# Vehicle_Circuit.net
KiCad netlist of a schematic drawn in Altium Designer
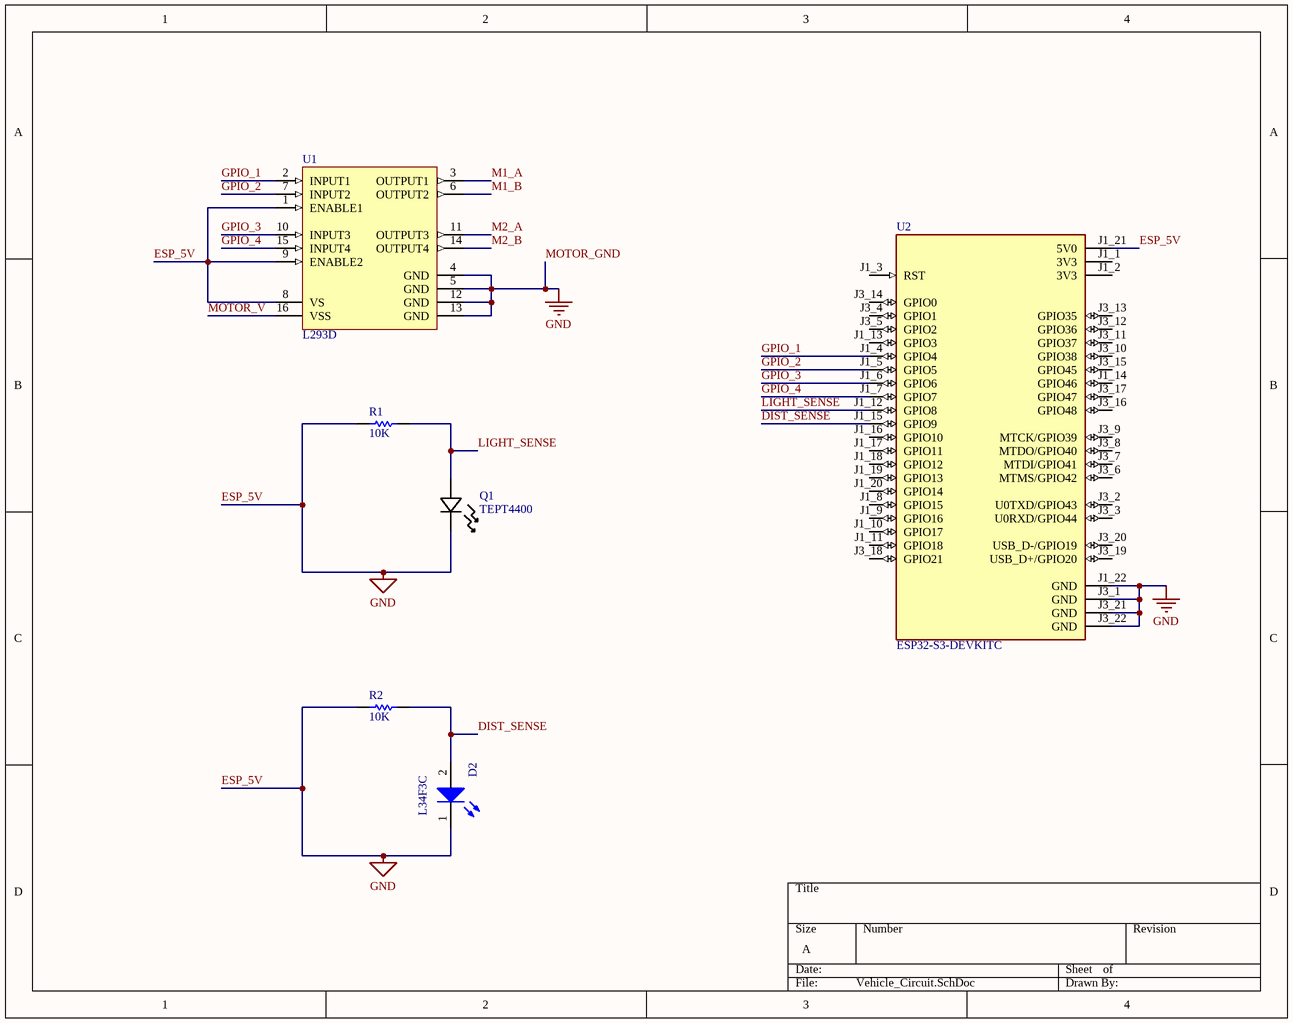
[diagram p0: Vehicle_Circuit.SchDoc]

(export (version "E")
  (design (tool "Eeschema 10.0.6"))
  (components
    (comp (ref "D2")
      (value "L34F3C")
      (footprint "WL-TIRW_D3.9H5.3")
      (description "WL-TIRW THT Infrared Round Waterclear")
      (libsource (lib "Altium Content Vault") (part "LED_Infrared_2A-1K"))
    )
    (comp (ref "Q1")
      (value "TEPT4400")
      (footprint "LED_TEPT4400_VIS")
      (description "PHOTO TRANS. 3MM  30DEG-e4")
      (fields (field (name "COPYRIGHT") "Copyright (C) 2026 Ultra Librarian. All rights reserved."))
      (libsource (lib "TEPT4400") (part "TEPT4400"))
    )
    (comp (ref "R1")
      (value "10K")
      (description "Resistor")
      (libsource (lib "Simulation Generic Components") (part "Resistor"))
    )
    (comp (ref "R2")
      (value "10K")
      (description "Resistor")
      (libsource (lib "Simulation Generic Components") (part "Resistor"))
    )
    (comp (ref "U1")
      (value "L293D")
      (footprint "STM-L293D-16")
      (description "Push-Pull Four Channel Driver with Diode, 4.5 to 36 V, -40 to 150 degC, 16-Pin PDIP, RoHS, Tube")
      (fields (field (name "MANUFACTURER") "STMicroelectronics"))
      (libsource (lib "Altium Content Vault") (part "STM-L293D-16"))
    )
    (comp (ref "U2")
      (value "ESP32-S3-DEVKITC")
      (footprint "XCVR_ESP32-S3-DEVKITC-1-N16R8V")
      (fields (field (name "MF") "Espressif Systems") (field (name "MP") "ESP32-S3-DEVKITC-1-N16R8V"))
      (libsource (lib "ESP32-S3-DEVKITC-1-N16R8V") (part "ESP32-S3-DEVKITC-1-N16R8V"))
    )
  )
  (nets
    (net (code "1") (name "/DIST_SENSE") (class "Default")
      (node (ref "D2") (pin "2") (pinfunction "A_2") (pintype "passive"))
      (node (ref "R2") (pin "2") (pinfunction "2_2") (pintype "passive"))
      (node (ref "U2") (pin "J1_15") (pinfunction "GPIO9_J1_15") (pintype "bidirectional"))
    )
    (net (code "2") (name "/GPIO_1") (class "Default")
      (node (ref "U1") (pin "2") (pinfunction "INPUT1_2") (pintype "input"))
      (node (ref "U2") (pin "J1_4") (pinfunction "GPIO4_J1_4") (pintype "bidirectional"))
    )
    (net (code "3") (name "/GPIO_2") (class "Default")
      (node (ref "U1") (pin "7") (pinfunction "INPUT2_7") (pintype "input"))
      (node (ref "U2") (pin "J1_5") (pinfunction "GPIO5_J1_5") (pintype "bidirectional"))
    )
    (net (code "4") (name "/GPIO_3") (class "Default")
      (node (ref "U1") (pin "10") (pinfunction "INPUT3_10") (pintype "input"))
      (node (ref "U2") (pin "J1_6") (pinfunction "GPIO6_J1_6") (pintype "bidirectional"))
    )
    (net (code "5") (name "/GPIO_4") (class "Default")
      (node (ref "U1") (pin "15") (pinfunction "INPUT4_15") (pintype "input"))
      (node (ref "U2") (pin "J1_7") (pinfunction "GPIO7_J1_7") (pintype "bidirectional"))
    )
    (net (code "6") (name "/LIGHT_SENSE") (class "Default")
      (node (ref "Q1") (pin "2") (pinfunction "2_2") (pintype "passive"))
      (node (ref "R1") (pin "2") (pinfunction "2_2") (pintype "passive"))
      (node (ref "U2") (pin "J1_12") (pinfunction "GPIO8_J1_12") (pintype "bidirectional"))
    )
    (net (code "7") (name "/M1_A") (class "Default")
      (node (ref "U1") (pin "3") (pinfunction "OUTPUT1_3") (pintype "output"))
    )
    (net (code "8") (name "/M1_B") (class "Default")
      (node (ref "U1") (pin "6") (pinfunction "OUTPUT2_6") (pintype "output"))
    )
    (net (code "9") (name "/M2_A") (class "Default")
      (node (ref "U1") (pin "11") (pinfunction "OUTPUT3_11") (pintype "output"))
    )
    (net (code "10") (name "/M2_B") (class "Default")
      (node (ref "U1") (pin "14") (pinfunction "OUTPUT4_14") (pintype "output"))
    )
    (net (code "11") (name "/MOTOR_V") (class "Default")
      (node (ref "U1") (pin "16") (pinfunction "VSS_16") (pintype "power_in"))
    )
    (net (code "12") (name "GND") (class "Default")
      (node (ref "D2") (pin "1") (pinfunction "K_1") (pintype "passive"))
      (node (ref "Q1") (pin "1") (pinfunction "1_1") (pintype "passive"))
      (node (ref "R1") (pin "1") (pinfunction "1_1") (pintype "passive"))
      (node (ref "R2") (pin "1") (pinfunction "1_1") (pintype "passive"))
      (node (ref "U1") (pin "1") (pinfunction "ENABLE1_1") (pintype "input"))
      (node (ref "U1") (pin "12") (pinfunction "GND_12") (pintype "power_in"))
      (node (ref "U1") (pin "13") (pinfunction "GND_13") (pintype "power_in"))
      (node (ref "U1") (pin "4") (pinfunction "GND_4") (pintype "power_in"))
      (node (ref "U1") (pin "5") (pinfunction "GND_5") (pintype "power_in"))
      (node (ref "U1") (pin "8") (pinfunction "VS_8") (pintype "power_in"))
      (node (ref "U1") (pin "9") (pinfunction "ENABLE2_9") (pintype "input"))
      (node (ref "U2") (pin "J1_21") (pinfunction "5V0_J1_21") (pintype "power_in"))
      (node (ref "U2") (pin "J1_22") (pinfunction "GND_J1_22") (pintype "power_in"))
      (node (ref "U2") (pin "J3_1") (pinfunction "GND_J3_1") (pintype "power_in"))
      (node (ref "U2") (pin "J3_21") (pinfunction "GND_J3_21") (pintype "power_in"))
      (node (ref "U2") (pin "J3_22") (pinfunction "GND_J3_22") (pintype "power_in"))
    )
    (net (code "13") (name "unconnected-(U2-3V3-PadJ1_1)") (class "Default")
      (node (ref "U2") (pin "J1_1") (pinfunction "3V3_J1_1") (pintype "power_in"))
    )
    (net (code "14") (name "unconnected-(U2-3V3-PadJ1_2)") (class "Default")
      (node (ref "U2") (pin "J1_2") (pinfunction "3V3_J1_2") (pintype "power_in"))
    )
    (net (code "15") (name "unconnected-(U2-GPIO0-PadJ3_14)") (class "Default")
      (node (ref "U2") (pin "J3_14") (pinfunction "GPIO0_J3_14") (pintype "bidirectional"))
    )
    (net (code "16") (name "unconnected-(U2-GPIO1-PadJ3_4)") (class "Default")
      (node (ref "U2") (pin "J3_4") (pinfunction "GPIO1_J3_4") (pintype "bidirectional"))
    )
    (net (code "17") (name "unconnected-(U2-GPIO2-PadJ3_5)") (class "Default")
      (node (ref "U2") (pin "J3_5") (pinfunction "GPIO2_J3_5") (pintype "bidirectional"))
    )
    (net (code "18") (name "unconnected-(U2-GPIO3-PadJ1_13)") (class "Default")
      (node (ref "U2") (pin "J1_13") (pinfunction "GPIO3_J1_13") (pintype "bidirectional"))
    )
    (net (code "19") (name "unconnected-(U2-GPIO10-PadJ1_16)") (class "Default")
      (node (ref "U2") (pin "J1_16") (pinfunction "GPIO10_J1_16") (pintype "bidirectional"))
    )
    (net (code "20") (name "unconnected-(U2-GPIO11-PadJ1_17)") (class "Default")
      (node (ref "U2") (pin "J1_17") (pinfunction "GPIO11_J1_17") (pintype "bidirectional"))
    )
    (net (code "21") (name "unconnected-(U2-GPIO12-PadJ1_18)") (class "Default")
      (node (ref "U2") (pin "J1_18") (pinfunction "GPIO12_J1_18") (pintype "bidirectional"))
    )
    (net (code "22") (name "unconnected-(U2-GPIO13-PadJ1_19)") (class "Default")
      (node (ref "U2") (pin "J1_19") (pinfunction "GPIO13_J1_19") (pintype "bidirectional"))
    )
    (net (code "23") (name "unconnected-(U2-GPIO14-PadJ1_20)") (class "Default")
      (node (ref "U2") (pin "J1_20") (pinfunction "GPIO14_J1_20") (pintype "bidirectional"))
    )
    (net (code "24") (name "unconnected-(U2-GPIO15-PadJ1_8)") (class "Default")
      (node (ref "U2") (pin "J1_8") (pinfunction "GPIO15_J1_8") (pintype "bidirectional"))
    )
    (net (code "25") (name "unconnected-(U2-GPIO16-PadJ1_9)") (class "Default")
      (node (ref "U2") (pin "J1_9") (pinfunction "GPIO16_J1_9") (pintype "bidirectional"))
    )
    (net (code "26") (name "unconnected-(U2-GPIO17-PadJ1_10)") (class "Default")
      (node (ref "U2") (pin "J1_10") (pinfunction "GPIO17_J1_10") (pintype "bidirectional"))
    )
    (net (code "27") (name "unconnected-(U2-GPIO18-PadJ1_11)") (class "Default")
      (node (ref "U2") (pin "J1_11") (pinfunction "GPIO18_J1_11") (pintype "bidirectional"))
    )
    (net (code "28") (name "unconnected-(U2-GPIO21-PadJ3_18)") (class "Default")
      (node (ref "U2") (pin "J3_18") (pinfunction "GPIO21_J3_18") (pintype "bidirectional"))
    )
    (net (code "29") (name "unconnected-(U2-GPIO35-PadJ3_13)") (class "Default")
      (node (ref "U2") (pin "J3_13") (pinfunction "GPIO35_J3_13") (pintype "bidirectional"))
    )
    (net (code "30") (name "unconnected-(U2-GPIO36-PadJ3_12)") (class "Default")
      (node (ref "U2") (pin "J3_12") (pinfunction "GPIO36_J3_12") (pintype "bidirectional"))
    )
    (net (code "31") (name "unconnected-(U2-GPIO37-PadJ3_11)") (class "Default")
      (node (ref "U2") (pin "J3_11") (pinfunction "GPIO37_J3_11") (pintype "bidirectional"))
    )
    (net (code "32") (name "unconnected-(U2-GPIO38-PadJ3_10)") (class "Default")
      (node (ref "U2") (pin "J3_10") (pinfunction "GPIO38_J3_10") (pintype "bidirectional"))
    )
    (net (code "33") (name "unconnected-(U2-GPIO45-PadJ3_15)") (class "Default")
      (node (ref "U2") (pin "J3_15") (pinfunction "GPIO45_J3_15") (pintype "bidirectional"))
    )
    (net (code "34") (name "unconnected-(U2-GPIO46-PadJ1_14)") (class "Default")
      (node (ref "U2") (pin "J1_14") (pinfunction "GPIO46_J1_14") (pintype "bidirectional"))
    )
    (net (code "35") (name "unconnected-(U2-GPIO47-PadJ3_17)") (class "Default")
      (node (ref "U2") (pin "J3_17") (pinfunction "GPIO47_J3_17") (pintype "bidirectional"))
    )
    (net (code "36") (name "unconnected-(U2-GPIO48-PadJ3_16)") (class "Default")
      (node (ref "U2") (pin "J3_16") (pinfunction "GPIO48_J3_16") (pintype "bidirectional"))
    )
    (net (code "37") (name "unconnected-(U2-MTCK{slash}GPIO39-PadJ3_9)") (class "Default")
      (node (ref "U2") (pin "J3_9") (pinfunction "MTCK/GPIO39_J3_9") (pintype "bidirectional"))
    )
    (net (code "38") (name "unconnected-(U2-MTDI{slash}GPIO41-PadJ3_7)") (class "Default")
      (node (ref "U2") (pin "J3_7") (pinfunction "MTDI/GPIO41_J3_7") (pintype "bidirectional"))
    )
    (net (code "39") (name "unconnected-(U2-MTDO{slash}GPIO40-PadJ3_8)") (class "Default")
      (node (ref "U2") (pin "J3_8") (pinfunction "MTDO/GPIO40_J3_8") (pintype "bidirectional"))
    )
    (net (code "40") (name "unconnected-(U2-MTMS{slash}GPIO42-PadJ3_6)") (class "Default")
      (node (ref "U2") (pin "J3_6") (pinfunction "MTMS/GPIO42_J3_6") (pintype "bidirectional"))
    )
    (net (code "41") (name "unconnected-(U2-RST-PadJ1_3)") (class "Default")
      (node (ref "U2") (pin "J1_3") (pinfunction "RST_J1_3") (pintype "input"))
    )
    (net (code "42") (name "unconnected-(U2-U0RXD{slash}GPIO44-PadJ3_3)") (class "Default")
      (node (ref "U2") (pin "J3_3") (pinfunction "U0RXD/GPIO44_J3_3") (pintype "bidirectional"))
    )
    (net (code "43") (name "unconnected-(U2-U0TXD{slash}GPIO43-PadJ3_2)") (class "Default")
      (node (ref "U2") (pin "J3_2") (pinfunction "U0TXD/GPIO43_J3_2") (pintype "bidirectional"))
    )
    (net (code "44") (name "unconnected-(U2-USB_D+{slash}GPIO20-PadJ3_19)") (class "Default")
      (node (ref "U2") (pin "J3_19") (pinfunction "USB_D+/GPIO20_J3_19") (pintype "bidirectional"))
    )
    (net (code "45") (name "unconnected-(U2-USB_D-{slash}GPIO19-PadJ3_20)") (class "Default")
      (node (ref "U2") (pin "J3_20") (pinfunction "USB_D-/GPIO19_J3_20") (pintype "bidirectional"))
    )
  )
)
